# umlma.net
KiCad netlist of a schematic drawn in EAGLE
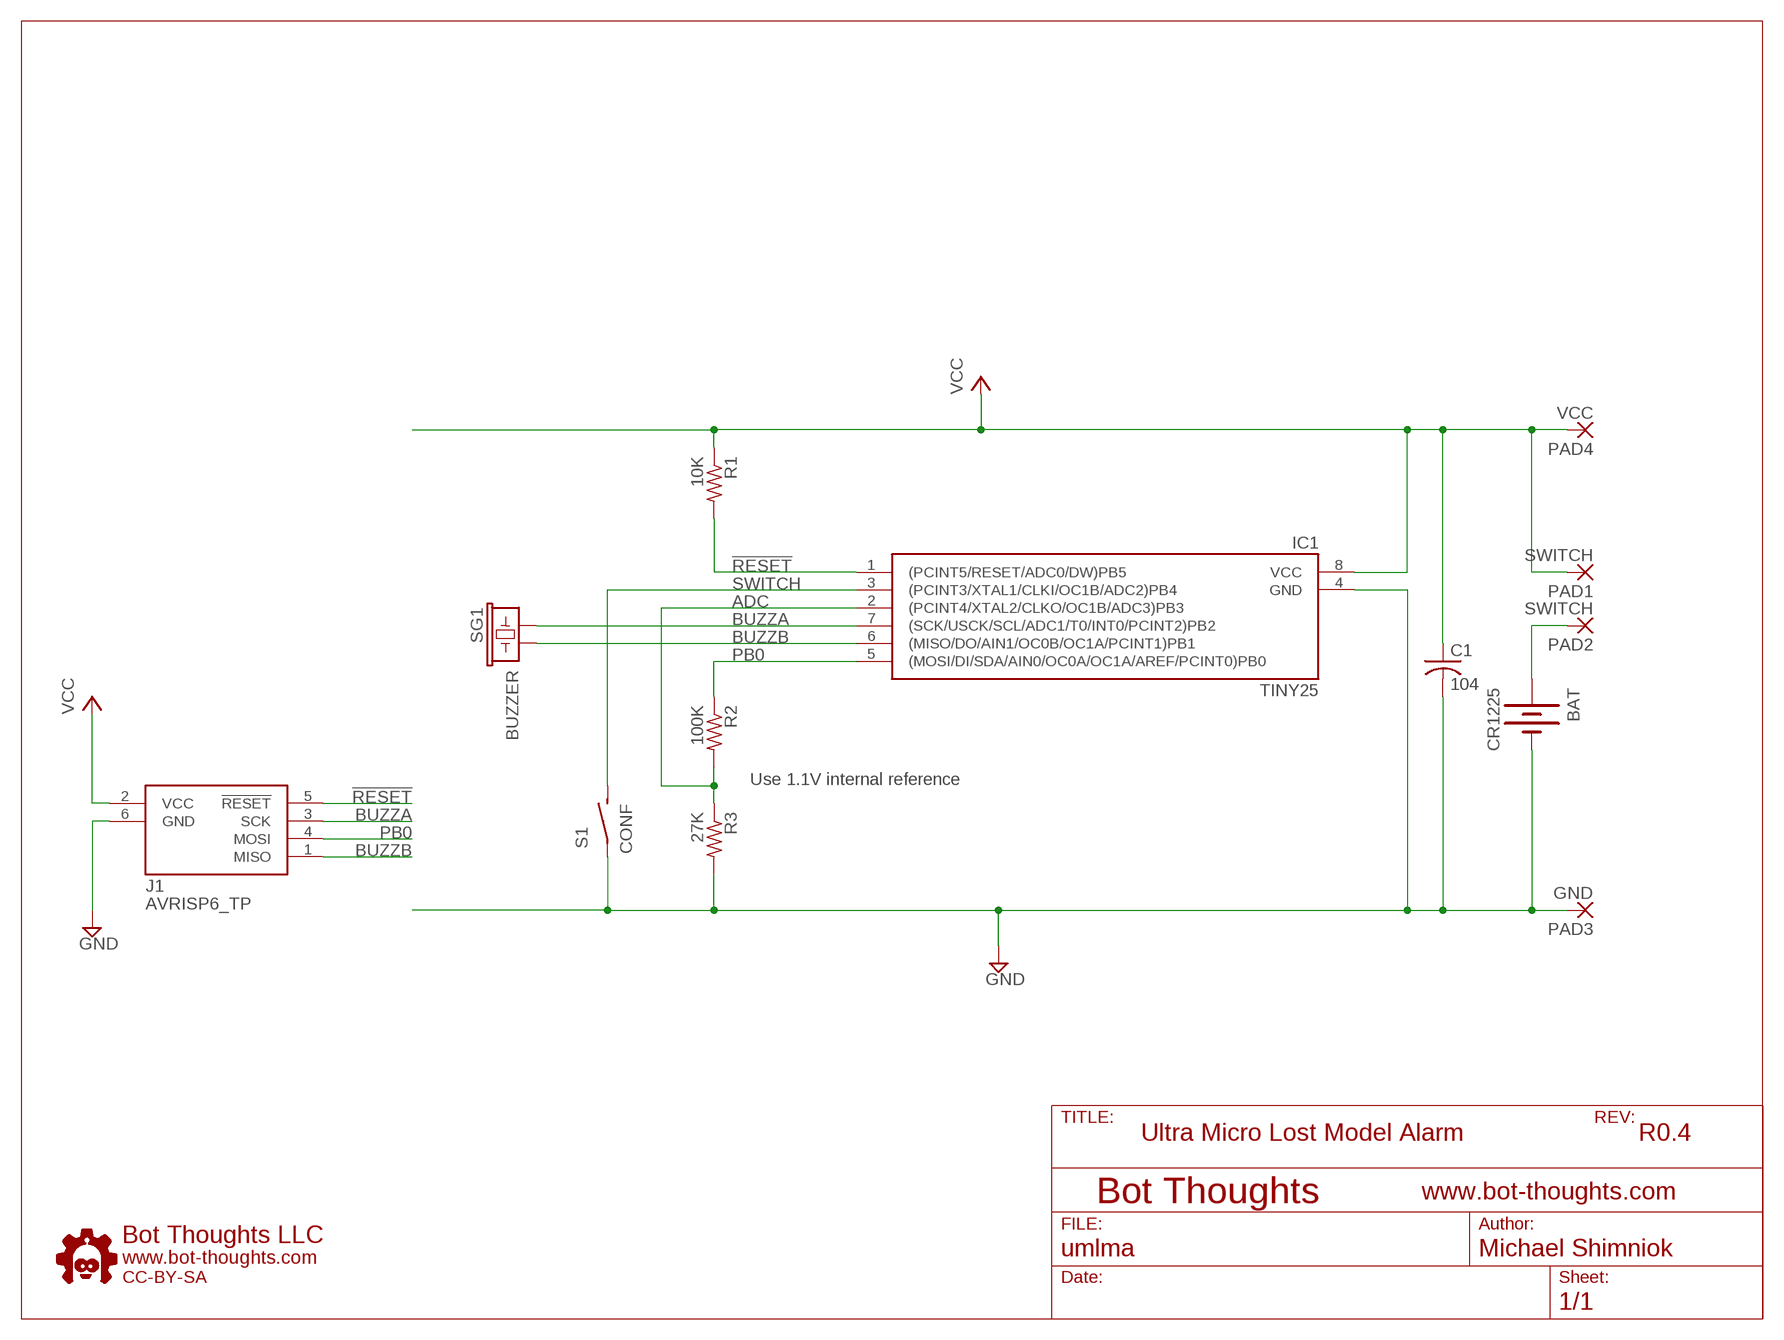
[diagram p0: schematic, sheet 1]

(export (version "E")
  (design (tool "Eeschema 10.0.6"))
  (components
    (comp (ref "BAT")
      (value "CR1225")
      (footprint "eagle-import:BATTCON_12MM_PTH")
      (libsource (lib "eagle-import") (part "BATTERY12PTH"))
    )
    (comp (ref "C1")
      (value "104")
      (footprint "eagle-import:C0603K")
      (fields (field (name "PARTNO") "GRM188R60J105KA01D"))
      (libsource (lib "eagle-import") (part "C-USC0603K"))
    )
    (comp (ref "IC1")
      (value "TINY25")
      (footprint "eagle-import:SOIC8N")
      (libsource (lib "eagle-import") (part "TINY25-20SSU"))
    )
    (comp (ref "J1")
      (value "AVRISP6_TP")
      (footprint "eagle-import:2X3_TP")
      (libsource (lib "eagle-import") (part "AVRISP6_TP"))
    )
    (comp (ref "PAD1")
      (value "SWITCH")
      (footprint "eagle-import:1,6_0,8")
      (libsource (lib "eagle-import") (part "WIREPAD1,6/0,8"))
    )
    (comp (ref "PAD2")
      (value "SWITCH")
      (footprint "eagle-import:1,6_0,8")
      (libsource (lib "eagle-import") (part "WIREPAD1,6/0,8"))
    )
    (comp (ref "PAD3")
      (value "GND")
      (footprint "eagle-import:1,6_0,8")
      (libsource (lib "eagle-import") (part "WIREPAD1,6/0,8"))
    )
    (comp (ref "PAD4")
      (value "VCC")
      (footprint "eagle-import:1,6_0,8")
      (libsource (lib "eagle-import") (part "WIREPAD1,6/0,8"))
    )
    (comp (ref "R1")
      (value "10K")
      (footprint "eagle-import:R0603")
      (fields (field (name "PARTNO") "ERJ-3GEYJ102V"))
      (libsource (lib "eagle-import") (part "R-US_R0603"))
    )
    (comp (ref "R2")
      (value "100K")
      (footprint "eagle-import:R0603")
      (fields (field (name "PARTNO") "ERJ-3GEYJ102V"))
      (libsource (lib "eagle-import") (part "R-US_R0603"))
    )
    (comp (ref "R3")
      (value "27K")
      (footprint "eagle-import:R0603")
      (fields (field (name "PARTNO") "ERJ-3GEYJ102V"))
      (libsource (lib "eagle-import") (part "R-US_R0603"))
    )
    (comp (ref "S1")
      (value "CONF")
      (footprint "eagle-import:3X4X2TACT")
      (libsource (lib "eagle-import") (part "SPST_3X4X2"))
    )
    (comp (ref "SG1")
      (value "BUZZER")
      (footprint "eagle-import:BUZZER_14MM_V_PTH")
      (fields (field (name "PARTNO") "AT-1438-TWT-R"))
      (libsource (lib "eagle-import") (part "BUZZER-AT-1438-TWT-R-VERT"))
    )
    (comp (ref "U$1")
      (value "BTLOGO-LOGO-SM")
      (footprint "eagle-import:BTLOGOS")
      (libsource (lib "eagle-import") (part "BTLOGO-LOGO-SM"))
    )
  )
  (nets
    (net (code "1") (name "/ADC") (class "Default")
      (node (ref "IC1") (pin "2") (pinfunction "(PCINT4/XTAL2/CLKO/OC1B/ADC3)PB3_2") (pintype "bidirectional"))
      (node (ref "R2") (pin "2") (pinfunction "2_2") (pintype "passive"))
      (node (ref "R3") (pin "1") (pinfunction "1_1") (pintype "passive"))
    )
    (net (code "2") (name "/BUZZA") (class "Default")
      (node (ref "IC1") (pin "7") (pinfunction "(SCK/USCK/SCL/ADC1/T0/INT0/PCINT2)PB2_7") (pintype "bidirectional"))
      (node (ref "J1") (pin "3") (pinfunction "SCK_3") (pintype "output"))
      (node (ref "SG1") (pin "P$5") (pinfunction "1_P$5") (pintype "passive"))
    )
    (net (code "3") (name "/BUZZB") (class "Default")
      (node (ref "IC1") (pin "6") (pinfunction "(MISO/DO/AIN1/OC0B/OC1A/PCINT1)PB1_6") (pintype "bidirectional"))
      (node (ref "J1") (pin "1") (pinfunction "MISO_1") (pintype "input"))
      (node (ref "SG1") (pin "P$6") (pinfunction "2_P$6") (pintype "passive"))
    )
    (net (code "4") (name "/PB0") (class "Default")
      (node (ref "IC1") (pin "5") (pinfunction "(MOSI/DI/SDA/AIN0/OC0A/OC1A/AREF/PCINT0)PB0_5") (pintype "bidirectional"))
      (node (ref "J1") (pin "4") (pinfunction "MOSI_4") (pintype "output"))
      (node (ref "R2") (pin "1") (pinfunction "1_1") (pintype "passive"))
    )
    (net (code "5") (name "/SWITCH") (class "Default")
      (node (ref "IC1") (pin "3") (pinfunction "(PCINT3/XTAL1/CLKI/OC1B/ADC2)PB4_3") (pintype "bidirectional"))
      (node (ref "S1") (pin "P$2") (pinfunction "S_P$2") (pintype "passive"))
    )
    (net (code "6") (name "/~{RESET}") (class "Default")
      (node (ref "IC1") (pin "1") (pinfunction "(PCINT5/RESET/ADC0/DW)PB5_1") (pintype "bidirectional"))
      (node (ref "J1") (pin "5") (pinfunction "~{RESET}_5") (pintype "output"))
      (node (ref "R1") (pin "2") (pinfunction "2_2") (pintype "passive"))
    )
    (net (code "7") (name "GND") (class "Default")
      (node (ref "BAT") (pin "GND") (pinfunction "-_GND") (pintype "power_in"))
      (node (ref "C1") (pin "2") (pinfunction "2_2") (pintype "passive"))
      (node (ref "IC1") (pin "4") (pinfunction "GND_4") (pintype "power_in"))
      (node (ref "J1") (pin "6") (pinfunction "GND_6") (pintype "power_in"))
      (node (ref "PAD3") (pin "1") (pinfunction "P_1") (pintype "passive"))
      (node (ref "R3") (pin "2") (pinfunction "2_2") (pintype "passive"))
      (node (ref "S1") (pin "P$1") (pinfunction "P_P$1") (pintype "passive"))
    )
    (net (code "8") (name "Net-(BAT-+)") (class "Default")
      (node (ref "BAT") (pin "VCC@1") (pinfunction "+_VCC@1") (pintype "power_in"))
      (node (ref "PAD2") (pin "1") (pinfunction "P_1") (pintype "passive"))
    )
    (net (code "9") (name "VCC") (class "Default")
      (node (ref "C1") (pin "1") (pinfunction "1_1") (pintype "passive"))
      (node (ref "IC1") (pin "8") (pinfunction "VCC_8") (pintype "power_in"))
      (node (ref "J1") (pin "2") (pinfunction "VCC_2") (pintype "power_in"))
      (node (ref "PAD1") (pin "1") (pinfunction "P_1") (pintype "passive"))
      (node (ref "PAD4") (pin "1") (pinfunction "P_1") (pintype "passive"))
      (node (ref "R1") (pin "1") (pinfunction "1_1") (pintype "passive"))
    )
  )
)
